# design.net
KiCad netlist of a schematic drawn in EasyEDA Pro
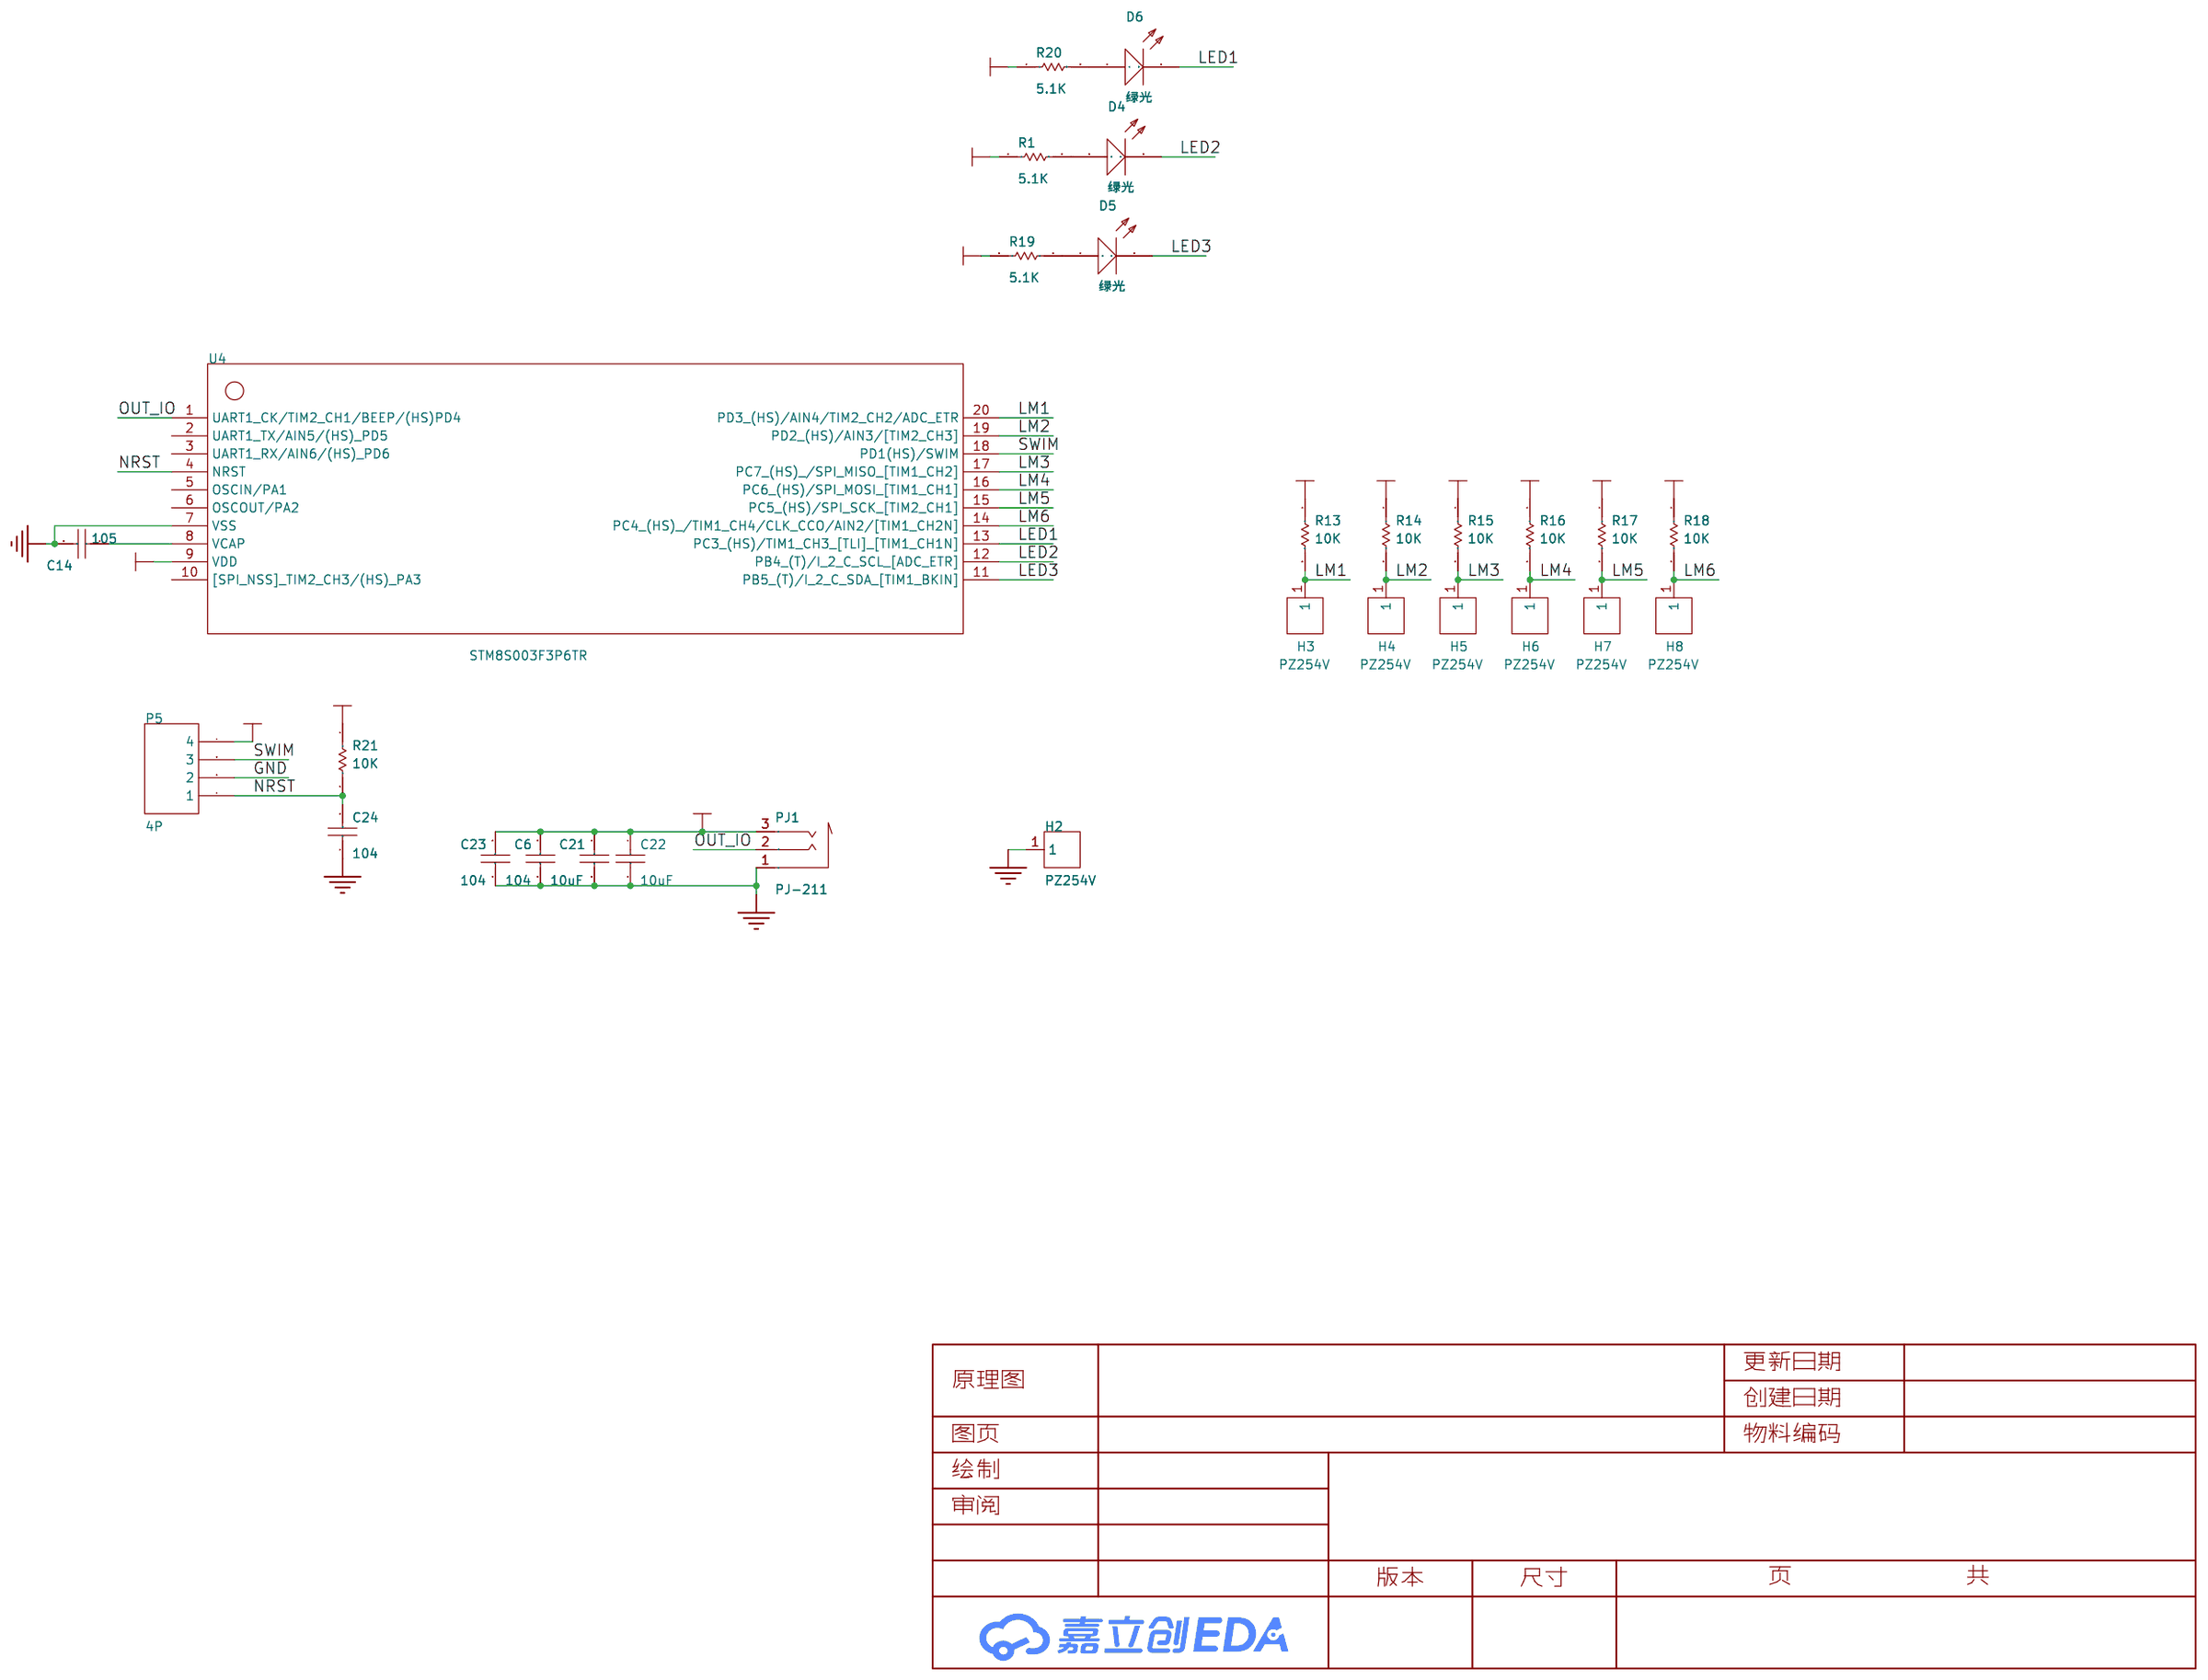
[diagram p0: schematic sheet]

(export (version "E")
  (design (tool "Eeschema 10.0.6"))
  (components
    (comp (ref "C6")
      (value "104")
      (footprint "easyedapro:0603C")
      (description "Capacitor (Semiconductor SIM Model)")
      (libsource (lib "easyedapro") (part "Cap Semi"))
    )
    (comp (ref "C14")
      (value "105")
      (footprint "easyedapro:0603C")
      (description "Capacitor (Semiconductor SIM Model)")
      (libsource (lib "easyedapro") (part "Cap Semi"))
    )
    (comp (ref "C21") (value "10uF") (libsource (lib "easyedapro") (part "CAP")))
    (comp (ref "C22") (value "10uF") (libsource (lib "easyedapro") (part "CAP")))
    (comp (ref "C23")
      (value "104")
      (footprint "easyedapro:0603C")
      (description "Capacitor (Semiconductor SIM Model)")
      (libsource (lib "easyedapro") (part "Cap Semi"))
    )
    (comp (ref "C24")
      (value "104")
      (footprint "easyedapro:0603C")
      (description "Capacitor (Semiconductor SIM Model)")
      (libsource (lib "easyedapro") (part "Cap Semi"))
    )
    (comp (ref "D4")
      (value "绿光")
      (footprint "easyedapro:0603LED")
      (libsource (lib "easyedapro") (part "LED"))
    )
    (comp (ref "D5")
      (value "绿光")
      (footprint "easyedapro:0603LED")
      (libsource (lib "easyedapro") (part "LED"))
    )
    (comp (ref "D6")
      (value "绿光")
      (footprint "easyedapro:0603LED")
      (libsource (lib "easyedapro") (part "LED"))
    )
    (comp (ref "H2")
      (value "PZ254V")
      (footprint "easyedapro:HDR-TH_1P-PZ254V-11-01P-YL")
      (description "排针2.54mm间距 直插 1x01位 黄色胶芯")
      (fields (field (name "Manufacturer") "XFCN(兴飞)"))
      (libsource (lib "easyedapro") (part "PZ254V-11-01P-YL"))
    )
    (comp (ref "H3")
      (value "PZ254V")
      (footprint "easyedapro:HDR-TH_1P-PZ254V-11-01P-YL")
      (description "排针2.54mm间距 直插 1x01位 黄色胶芯")
      (fields (field (name "Manufacturer") "XFCN(兴飞)"))
      (libsource (lib "easyedapro") (part "PZ254V-11-01P-YL"))
    )
    (comp (ref "H4")
      (value "PZ254V")
      (footprint "easyedapro:HDR-TH_1P-PZ254V-11-01P-YL")
      (description "排针2.54mm间距 直插 1x01位 黄色胶芯")
      (fields (field (name "Manufacturer") "XFCN(兴飞)"))
      (libsource (lib "easyedapro") (part "PZ254V-11-01P-YL"))
    )
    (comp (ref "H5")
      (value "PZ254V")
      (footprint "easyedapro:HDR-TH_1P-PZ254V-11-01P-YL")
      (description "排针2.54mm间距 直插 1x01位 黄色胶芯")
      (fields (field (name "Manufacturer") "XFCN(兴飞)"))
      (libsource (lib "easyedapro") (part "PZ254V-11-01P-YL"))
    )
    (comp (ref "H6")
      (value "PZ254V")
      (footprint "easyedapro:HDR-TH_1P-PZ254V-11-01P-YL")
      (description "排针2.54mm间距 直插 1x01位 黄色胶芯")
      (fields (field (name "Manufacturer") "XFCN(兴飞)"))
      (libsource (lib "easyedapro") (part "PZ254V-11-01P-YL"))
    )
    (comp (ref "H7")
      (value "PZ254V")
      (footprint "easyedapro:HDR-TH_1P-PZ254V-11-01P-YL")
      (description "排针2.54mm间距 直插 1x01位 黄色胶芯")
      (fields (field (name "Manufacturer") "XFCN(兴飞)"))
      (libsource (lib "easyedapro") (part "PZ254V-11-01P-YL"))
    )
    (comp (ref "H8")
      (value "PZ254V")
      (footprint "easyedapro:HDR-TH_1P-PZ254V-11-01P-YL")
      (description "排针2.54mm间距 直插 1x01位 黄色胶芯")
      (fields (field (name "Manufacturer") "XFCN(兴飞)"))
      (libsource (lib "easyedapro") (part "PZ254V-11-01P-YL"))
    )
    (comp (ref "P5") (value "4P") (libsource (lib "easyedapro") (part "4P")))
    (comp (ref "PJ1")
      (value "PJ-211")
      (footprint "easyedapro:AUDIO-TH_PJ-211")
      (description "连接器类型:2.5mm耳机座;额定电流:500mA;额定电压:30V;触头材质:铜;触头镀层:银;工作温度范围:-30°C~+70°C;")
      (fields (field (name "Manufacturer") "SHOU HAN(首韩)"))
      (libsource (lib "easyedapro") (part "PJ-211"))
    )
    (comp (ref "R1")
      (value "5.1K")
      (footprint "easyedapro:0603R")
      (description "Resistor")
      (libsource (lib "easyedapro") (part "RES"))
    )
    (comp (ref "R13")
      (value "10K")
      (footprint "easyedapro:0603R")
      (description "Resistor")
      (libsource (lib "easyedapro") (part "RES"))
    )
    (comp (ref "R14")
      (value "10K")
      (footprint "easyedapro:0603R")
      (description "Resistor")
      (libsource (lib "easyedapro") (part "RES"))
    )
    (comp (ref "R15")
      (value "10K")
      (footprint "easyedapro:0603R")
      (description "Resistor")
      (libsource (lib "easyedapro") (part "RES"))
    )
    (comp (ref "R16")
      (value "10K")
      (footprint "easyedapro:0603R")
      (description "Resistor")
      (libsource (lib "easyedapro") (part "RES"))
    )
    (comp (ref "R17")
      (value "10K")
      (footprint "easyedapro:0603R")
      (description "Resistor")
      (libsource (lib "easyedapro") (part "RES"))
    )
    (comp (ref "R18")
      (value "10K")
      (footprint "easyedapro:0603R")
      (description "Resistor")
      (libsource (lib "easyedapro") (part "RES"))
    )
    (comp (ref "R19")
      (value "5.1K")
      (footprint "easyedapro:0603R")
      (description "Resistor")
      (libsource (lib "easyedapro") (part "RES"))
    )
    (comp (ref "R20")
      (value "5.1K")
      (footprint "easyedapro:0603R")
      (description "Resistor")
      (libsource (lib "easyedapro") (part "RES"))
    )
    (comp (ref "R21")
      (value "10K")
      (footprint "easyedapro:0603R")
      (description "Resistor")
      (libsource (lib "easyedapro") (part "RES"))
    )
    (comp (ref "U4")
      (value "STM8S003F3P6TR")
      (footprint "easyedapro:TSSOP-20_L6.5-W4.4-P0.65-LS6.4-BL")
      (description "CPU内核:STM8;主频（MAX):16MHz;工作电压:2.95V~ 5.5V;")
      (fields (field (name "Manufacturer") "ST(意法半导体)"))
      (libsource (lib "easyedapro") (part "STM8S003F3P6TR"))
    )
  )
  (nets
    (net (code "1") (name "/LED1") (class "Default")
      (node (ref "D6") (pin "2") (pinfunction "2_2") (pintype "unspecified"))
      (node (ref "U4") (pin "13") (pinfunction "PC3_(HS)/TIM1_CH3_[TLI]_[TIM1_CH1N]_13") (pintype "input"))
    )
    (net (code "2") (name "/LED2") (class "Default")
      (node (ref "D4") (pin "2") (pinfunction "2_2") (pintype "unspecified"))
      (node (ref "U4") (pin "12") (pinfunction "PB4_(T)/I_2_C_SCL_[ADC_ETR]_12") (pintype "input"))
    )
    (net (code "3") (name "/LED3") (class "Default")
      (node (ref "D5") (pin "2") (pinfunction "2_2") (pintype "unspecified"))
      (node (ref "U4") (pin "11") (pinfunction "PB5_(T)/I_2_C_SDA_[TIM1_BKIN]_11") (pintype "input"))
    )
    (net (code "4") (name "/LM1") (class "Default")
      (node (ref "H3") (pin "1") (pinfunction "1_1") (pintype "unspecified"))
      (node (ref "R13") (pin "2") (pinfunction "2_2") (pintype "unspecified"))
      (node (ref "U4") (pin "20") (pinfunction "PD3_(HS)/AIN4/TIM2_CH2/ADC_ETR_20") (pintype "input"))
    )
    (net (code "5") (name "/LM2") (class "Default")
      (node (ref "H4") (pin "1") (pinfunction "1_1") (pintype "unspecified"))
      (node (ref "R14") (pin "2") (pinfunction "2_2") (pintype "unspecified"))
      (node (ref "U4") (pin "19") (pinfunction "PD2_(HS)/AIN3/[TIM2_CH3]_19") (pintype "input"))
    )
    (net (code "6") (name "/LM3") (class "Default")
      (node (ref "H5") (pin "1") (pinfunction "1_1") (pintype "unspecified"))
      (node (ref "R15") (pin "2") (pinfunction "2_2") (pintype "unspecified"))
      (node (ref "U4") (pin "17") (pinfunction "PC7_(HS)_/SPI_MISO_[TIM1_CH2]_17") (pintype "input"))
    )
    (net (code "7") (name "/LM4") (class "Default")
      (node (ref "H6") (pin "1") (pinfunction "1_1") (pintype "unspecified"))
      (node (ref "R16") (pin "2") (pinfunction "2_2") (pintype "unspecified"))
      (node (ref "U4") (pin "16") (pinfunction "PC6_(HS)/SPI_MOSI_[TIM1_CH1]_16") (pintype "input"))
    )
    (net (code "8") (name "/LM5") (class "Default")
      (node (ref "H7") (pin "1") (pinfunction "1_1") (pintype "unspecified"))
      (node (ref "R17") (pin "2") (pinfunction "2_2") (pintype "unspecified"))
      (node (ref "U4") (pin "15") (pinfunction "PC5_(HS)/SPI_SCK_[TIM2_CH1]_15") (pintype "input"))
    )
    (net (code "9") (name "/LM6") (class "Default")
      (node (ref "H8") (pin "1") (pinfunction "1_1") (pintype "unspecified"))
      (node (ref "R18") (pin "2") (pinfunction "2_2") (pintype "unspecified"))
      (node (ref "U4") (pin "14") (pinfunction "PC4_(HS)_/TIM1_CH4/CLK_CCO/AIN2/[TIM1_CH2N]_14") (pintype "input"))
    )
    (net (code "10") (name "/NRST") (class "Default")
      (node (ref "C24") (pin "2") (pinfunction "2_2") (pintype "unspecified"))
      (node (ref "P5") (pin "1") (pinfunction "1_1") (pintype "input"))
      (node (ref "R21") (pin "2") (pinfunction "2_2") (pintype "unspecified"))
      (node (ref "U4") (pin "4") (pinfunction "NRST_4") (pintype "input"))
    )
    (net (code "11") (name "/OUT_IO") (class "Default")
      (node (ref "PJ1") (pin "2") (pinfunction "2_2") (pintype "unspecified"))
      (node (ref "U4") (pin "1") (pinfunction "UART1_CK/TIM2_CH1/BEEP/(HS)PD4_1") (pintype "input"))
    )
    (net (code "12") (name "/SWIM") (class "Default")
      (node (ref "P5") (pin "3") (pinfunction "3_3") (pintype "input"))
      (node (ref "U4") (pin "18") (pinfunction "PD1(HS)/SWIM_18") (pintype "input"))
    )
    (net (code "13") (name "5V") (class "Default")
      (node (ref "C21") (pin "1") (pinfunction "1_1") (pintype "input"))
      (node (ref "C22") (pin "1") (pinfunction "1_1") (pintype "input"))
      (node (ref "C23") (pin "2") (pinfunction "2_2") (pintype "unspecified"))
      (node (ref "C6") (pin "2") (pinfunction "2_2") (pintype "unspecified"))
      (node (ref "P5") (pin "4") (pinfunction "4_4") (pintype "input"))
      (node (ref "PJ1") (pin "3") (pinfunction "3_3") (pintype "unspecified"))
      (node (ref "R1") (pin "1") (pinfunction "1_1") (pintype "unspecified"))
      (node (ref "R13") (pin "1") (pinfunction "1_1") (pintype "unspecified"))
      (node (ref "R14") (pin "1") (pinfunction "1_1") (pintype "unspecified"))
      (node (ref "R15") (pin "1") (pinfunction "1_1") (pintype "unspecified"))
      (node (ref "R16") (pin "1") (pinfunction "1_1") (pintype "unspecified"))
      (node (ref "R17") (pin "1") (pinfunction "1_1") (pintype "unspecified"))
      (node (ref "R18") (pin "1") (pinfunction "1_1") (pintype "unspecified"))
      (node (ref "R19") (pin "1") (pinfunction "1_1") (pintype "unspecified"))
      (node (ref "R20") (pin "1") (pinfunction "1_1") (pintype "unspecified"))
      (node (ref "R21") (pin "1") (pinfunction "1_1") (pintype "unspecified"))
      (node (ref "U4") (pin "9") (pinfunction "VDD_9") (pintype "input"))
    )
    (net (code "14") (name "GND") (class "Default")
      (node (ref "C14") (pin "2") (pinfunction "2_2") (pintype "unspecified"))
      (node (ref "C21") (pin "2") (pinfunction "2_2") (pintype "input"))
      (node (ref "C22") (pin "2") (pinfunction "2_2") (pintype "input"))
      (node (ref "C23") (pin "1") (pinfunction "1_1") (pintype "unspecified"))
      (node (ref "C24") (pin "1") (pinfunction "1_1") (pintype "unspecified"))
      (node (ref "C6") (pin "1") (pinfunction "1_1") (pintype "unspecified"))
      (node (ref "H2") (pin "1") (pinfunction "1_1") (pintype "unspecified"))
      (node (ref "P5") (pin "2") (pinfunction "2_2") (pintype "input"))
      (node (ref "PJ1") (pin "1") (pinfunction "1_1") (pintype "unspecified"))
      (node (ref "U4") (pin "7") (pinfunction "VSS_7") (pintype "input"))
    )
    (net (code "15") (name "Net-(D4-Pad1)") (class "Default")
      (node (ref "D4") (pin "1") (pinfunction "1_1") (pintype "unspecified"))
      (node (ref "R1") (pin "2") (pinfunction "2_2") (pintype "unspecified"))
    )
    (net (code "16") (name "Net-(D5-Pad1)") (class "Default")
      (node (ref "D5") (pin "1") (pinfunction "1_1") (pintype "unspecified"))
      (node (ref "R19") (pin "2") (pinfunction "2_2") (pintype "unspecified"))
    )
    (net (code "17") (name "Net-(D6-Pad1)") (class "Default")
      (node (ref "D6") (pin "1") (pinfunction "1_1") (pintype "unspecified"))
      (node (ref "R20") (pin "2") (pinfunction "2_2") (pintype "unspecified"))
    )
    (net (code "18") (name "Net-(U4-VCAP)") (class "Default")
      (node (ref "C14") (pin "1") (pinfunction "1_1") (pintype "unspecified"))
      (node (ref "U4") (pin "8") (pinfunction "VCAP_8") (pintype "input"))
    )
    (net (code "19") (name "unconnected-(U4-OSCIN{slash}PA1-Pad5)") (class "Default")
      (node (ref "U4") (pin "5") (pinfunction "OSCIN/PA1_5") (pintype "input"))
    )
    (net (code "20") (name "unconnected-(U4-OSCOUT{slash}PA2-Pad6)") (class "Default")
      (node (ref "U4") (pin "6") (pinfunction "OSCOUT/PA2_6") (pintype "input"))
    )
    (net (code "21") (name "unconnected-(U4-UART1_RX{slash}AIN6{slash}(HS)_PD6-Pad3)") (class "Default")
      (node (ref "U4") (pin "3") (pinfunction "UART1_RX/AIN6/(HS)_PD6_3") (pintype "input"))
    )
    (net (code "22") (name "unconnected-(U4-UART1_TX{slash}AIN5{slash}(HS)_PD5-Pad2)") (class "Default")
      (node (ref "U4") (pin "2") (pinfunction "UART1_TX/AIN5/(HS)_PD5_2") (pintype "input"))
    )
    (net (code "23") (name "unconnected-(U4-[SPI_NSS]_TIM2_CH3{slash}(HS)_PA3-Pad10)") (class "Default")
      (node (ref "U4") (pin "10") (pinfunction "[SPI_NSS]_TIM2_CH3/(HS)_PA3_10") (pintype "input"))
    )
  )
)
